# Color_Sorter_PROTOTYPE_v3_DMJ_Edit.net
KiCad netlist of a schematic drawn in EAGLE
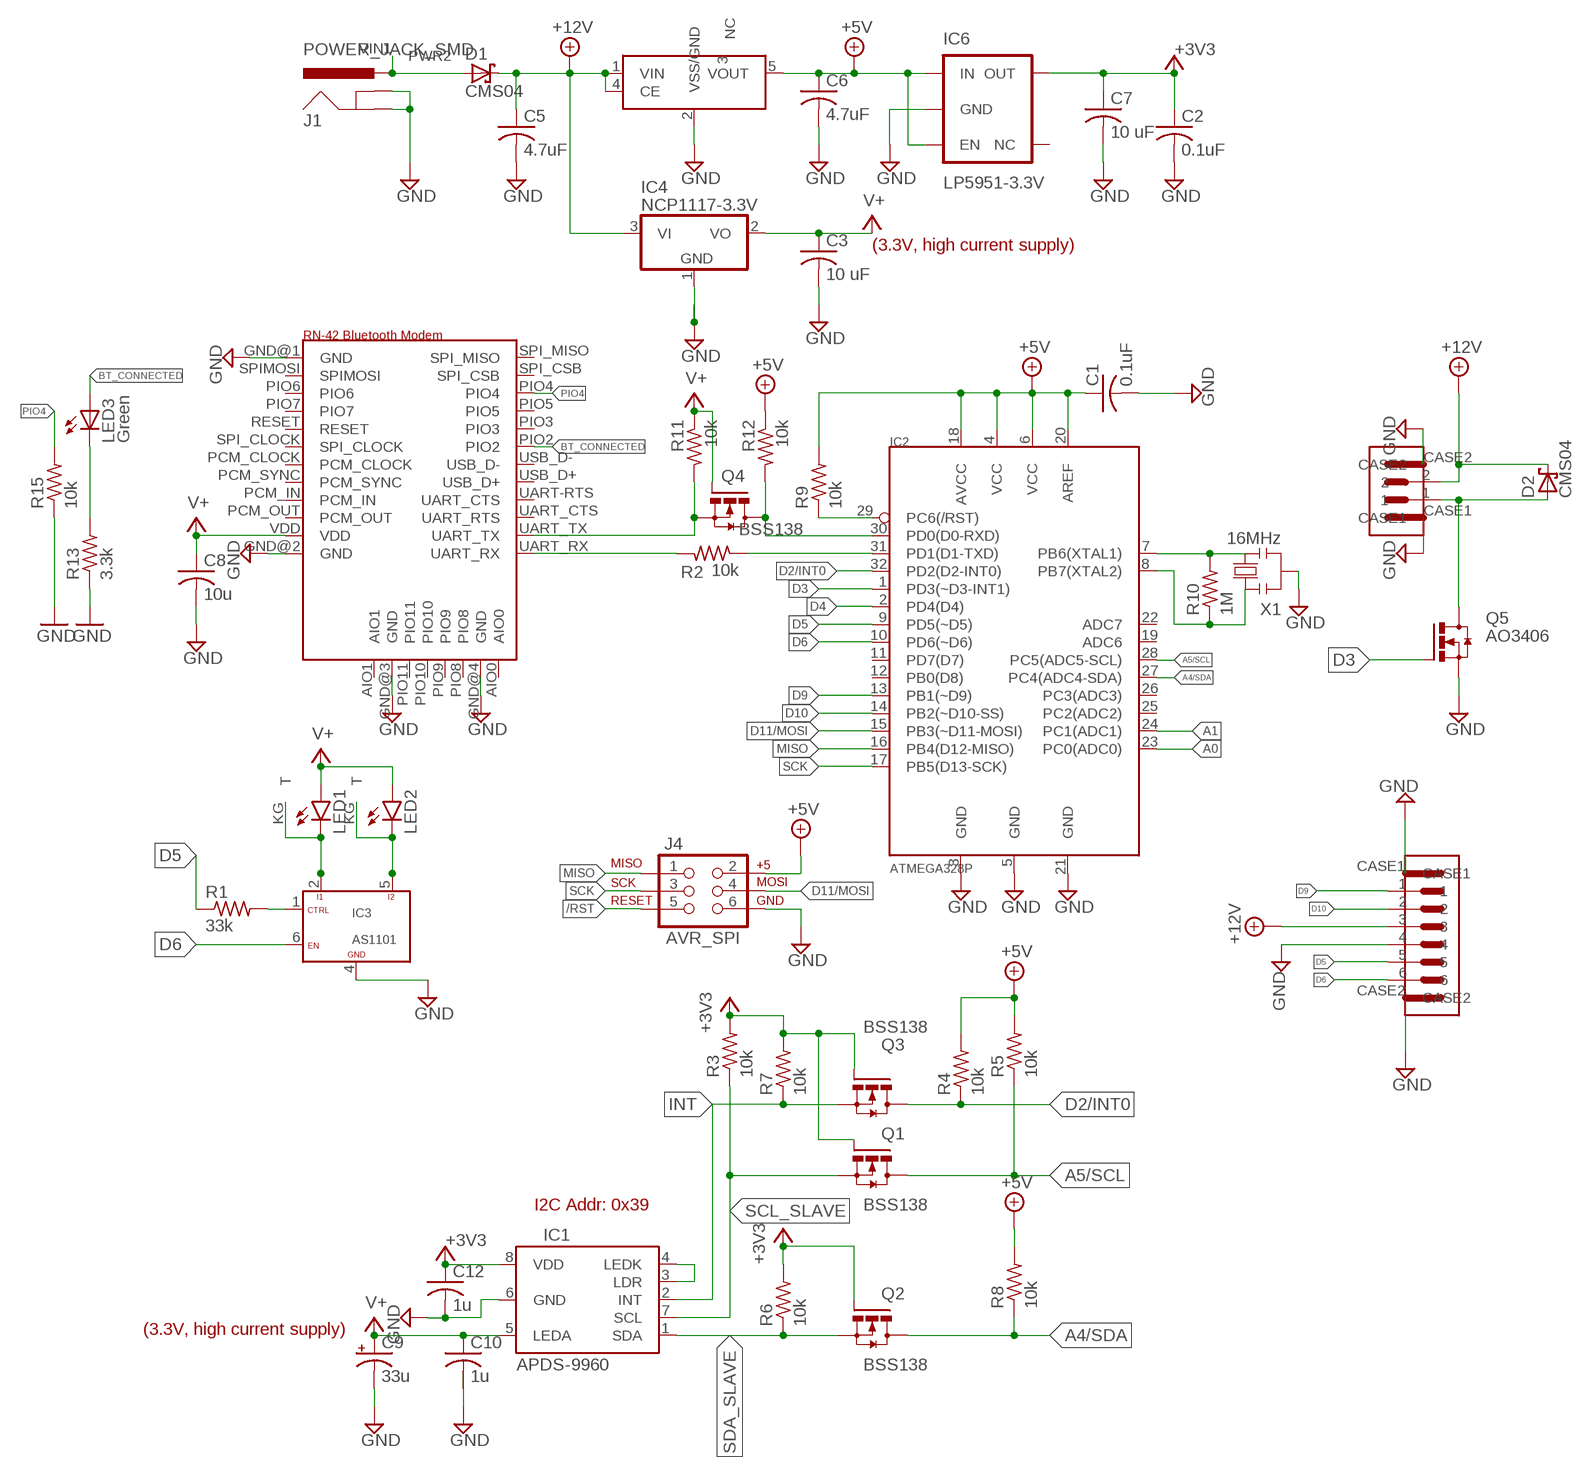
[diagram p0: schematic, sheet 1]

(export (version "E")
  (design (tool "Eeschema 10.0.6"))
  (components
    (comp (ref "A1")
      (value "RN-42_BLUETOOTH")
      (footprint "eagle-import:RN-42")
      (libsource (lib "eagle-import") (part "RN-42_BLUETOOTH"))
    )
    (comp (ref "C1")
      (value "0.1uF")
      (footprint "eagle-import:C0805")
      (libsource (lib "eagle-import") (part "C-USC0805"))
    )
    (comp (ref "C2")
      (value "0.1uF")
      (footprint "eagle-import:C0805")
      (libsource (lib "eagle-import") (part "C-USC0805"))
    )
    (comp (ref "C3")
      (value "10 uF")
      (footprint "eagle-import:C0805")
      (libsource (lib "eagle-import") (part "C-USC0805"))
    )
    (comp (ref "C5")
      (value "4.7uF")
      (footprint "eagle-import:C0805")
      (libsource (lib "eagle-import") (part "C-USC0805"))
    )
    (comp (ref "C6")
      (value "4.7uF")
      (footprint "eagle-import:C0805")
      (libsource (lib "eagle-import") (part "C-USC0805"))
    )
    (comp (ref "C7")
      (value "10 uF")
      (footprint "eagle-import:C0805")
      (libsource (lib "eagle-import") (part "C-USC0805"))
    )
    (comp (ref "C8")
      (value "10u")
      (footprint "eagle-import:C0805")
      (libsource (lib "eagle-import") (part "C-USC0805"))
    )
    (comp (ref "C9")
      (value "33u")
      (footprint "eagle-import:CT7343")
      (libsource (lib "eagle-import") (part "CPOL-USCT7343"))
    )
    (comp (ref "C10")
      (value "1u")
      (footprint "eagle-import:C0805")
      (libsource (lib "eagle-import") (part "C-USC0805"))
    )
    (comp (ref "C12")
      (value "1u")
      (footprint "eagle-import:C0805")
      (libsource (lib "eagle-import") (part "C-USC0805"))
    )
    (comp (ref "D1")
      (value "CMS04")
      (footprint "eagle-import:3-4E1A")
      (libsource (lib "eagle-import") (part "CMS04_SCHOTTKY"))
    )
    (comp (ref "D2")
      (value "CMS04")
      (footprint "eagle-import:3-4E1A")
      (libsource (lib "eagle-import") (part "CMS04_SCHOTTKY"))
    )
    (comp (ref "IC1")
      (value "APDS-9960")
      (footprint "eagle-import:SPARKFUN-SENSORS_APDS-9960")
      (libsource (lib "eagle-import") (part "SPARKFUN-SENSORS_APDS-9960"))
    )
    (comp (ref "IC2")
      (value "ATMEGA328P")
      (footprint "eagle-import:TQFP-32")
      (libsource (lib "eagle-import") (part "ATMEGA328P_TQFP"))
    )
    (comp (ref "IC3")
      (value "AS1101")
      (footprint "eagle-import:SC70-6")
      (libsource (lib "eagle-import") (part "AS1101-T"))
    )
    (comp (ref "IC4")
      (value "NCP1117-3.3V")
      (footprint "eagle-import:SOT-223")
      (libsource (lib "eagle-import") (part "NCP1117_REGULATOR"))
    )
    (comp (ref "IC5")
      (value "XC6701-5V")
      (footprint "eagle-import:DMJ_LINEAR_SOT23-5")
      (libsource (lib "eagle-import") (part "DMJ_LINEAR_XC6701B502"))
    )
    (comp (ref "IC6")
      (value "LP5951-3.3V")
      (footprint "eagle-import:SOT23-5")
      (libsource (lib "eagle-import") (part "LP5951-3.3V"))
    )
    (comp (ref "J1")
      (value "POWER_JACK_SMD")
      (footprint "eagle-import:SMD_POWER_JACK")
      (libsource (lib "eagle-import") (part "POWER_JACK_SMD"))
    )
    (comp (ref "J4")
      (value "AVR_SPI")
      (footprint "eagle-import:2X3")
      (libsource (lib "eagle-import") (part "AVR_SPI_PRG_6PTH"))
    )
    (comp (ref "LED1")
      (value "LED_SAMSUNG_SPMWHT541MD7WATMS0")
      (footprint "eagle-import:LED_SAMSUNG_SPMWHT541MD7WATMS0")
      (libsource (lib "eagle-import") (part "LED_SAMSUNG_SPMWHT541MD7WATMS0"))
    )
    (comp (ref "LED2")
      (value "LED_SAMSUNG_SPMWHT541MD7WATMS0")
      (footprint "eagle-import:LED_SAMSUNG_SPMWHT541MD7WATMS0")
      (libsource (lib "eagle-import") (part "LED_SAMSUNG_SPMWHT541MD7WATMS0"))
    )
    (comp (ref "LED3")
      (value "Green")
      (footprint "eagle-import:LED-1206")
      (libsource (lib "eagle-import") (part "LED1206"))
    )
    (comp (ref "Q1")
      (value "BSS138")
      (footprint "eagle-import:BE-420-CUSTOM-PARTS_SOT-23")
      (libsource (lib "eagle-import") (part "BE-420-CUSTOM-PARTS_BSS138_N_CHANNEL_MOSFET"))
    )
    (comp (ref "Q2")
      (value "BSS138")
      (footprint "eagle-import:BE-420-CUSTOM-PARTS_SOT-23")
      (libsource (lib "eagle-import") (part "BE-420-CUSTOM-PARTS_BSS138_N_CHANNEL_MOSFET"))
    )
    (comp (ref "Q3")
      (value "BSS138")
      (footprint "eagle-import:BE-420-CUSTOM-PARTS_SOT-23")
      (libsource (lib "eagle-import") (part "BE-420-CUSTOM-PARTS_BSS138_N_CHANNEL_MOSFET"))
    )
    (comp (ref "Q4")
      (value "BSS138")
      (footprint "eagle-import:BE-420-CUSTOM-PARTS_SOT-23")
      (libsource (lib "eagle-import") (part "BE-420-CUSTOM-PARTS_BSS138_N_CHANNEL_MOSFET"))
    )
    (comp (ref "Q5")
      (value "AO3406")
      (footprint "eagle-import:SOT-23-3")
      (libsource (lib "eagle-import") (part "N_PWR_MOSFET_AO3406"))
    )
    (comp (ref "R1")
      (value "33k")
      (footprint "eagle-import:R0805")
      (libsource (lib "eagle-import") (part "R-US_R0805"))
    )
    (comp (ref "R2")
      (value "10k")
      (footprint "eagle-import:R0805")
      (libsource (lib "eagle-import") (part "R-US_R0805"))
    )
    (comp (ref "R3")
      (value "10k")
      (footprint "eagle-import:R0805")
      (libsource (lib "eagle-import") (part "R-US_R0805"))
    )
    (comp (ref "R4")
      (value "10k")
      (footprint "eagle-import:R0805")
      (libsource (lib "eagle-import") (part "R-US_R0805"))
    )
    (comp (ref "R5")
      (value "10k")
      (footprint "eagle-import:R0805")
      (libsource (lib "eagle-import") (part "R-US_R0805"))
    )
    (comp (ref "R6")
      (value "10k")
      (footprint "eagle-import:R0805")
      (libsource (lib "eagle-import") (part "R-US_R0805"))
    )
    (comp (ref "R7")
      (value "10k")
      (footprint "eagle-import:R0805")
      (libsource (lib "eagle-import") (part "R-US_R0805"))
    )
    (comp (ref "R8")
      (value "10k")
      (footprint "eagle-import:R0805")
      (libsource (lib "eagle-import") (part "R-US_R0805"))
    )
    (comp (ref "R9")
      (value "10k")
      (footprint "eagle-import:R0805")
      (libsource (lib "eagle-import") (part "R-US_R0805"))
    )
    (comp (ref "R10")
      (value "1M")
      (footprint "eagle-import:R0805")
      (libsource (lib "eagle-import") (part "R-US_R0805"))
    )
    (comp (ref "R11")
      (value "10k")
      (footprint "eagle-import:R0805")
      (libsource (lib "eagle-import") (part "R-US_R0805"))
    )
    (comp (ref "R12")
      (value "10k")
      (footprint "eagle-import:R0805")
      (libsource (lib "eagle-import") (part "R-US_R0805"))
    )
    (comp (ref "R13")
      (value "3.3k")
      (footprint "eagle-import:R0805")
      (libsource (lib "eagle-import") (part "R-US_R0805"))
    )
    (comp (ref "R15")
      (value "10k")
      (footprint "eagle-import:R0805")
      (libsource (lib "eagle-import") (part "R-US_R0805"))
    )
    (comp (ref "U$4")
      (value "1A-JENKINS-PHOENIX-CONTACT-CONNECTORS_1A_JENKINS_2013_6PIN_SMD_PHOENIX_CONTACT")
      (footprint "eagle-import:1A-JENKINS-PHOENIX-CONTACT-CONNECTORS_1A_JENKINS_2013_6-PIN-R_A_PHOENIX_SMD")
      (libsource (lib "eagle-import") (part "1A-JENKINS-PHOENIX-CONTACT-CONNECTORS_1A_JENKINS_2013_6PIN_SMD_PHOENIX_CONTACT"))
    )
    (comp (ref "U$7")
      (value "1A_JENKINS_2013_2PIN_SMD_PHOENIX_CONTACT")
      (footprint "eagle-import:1A_JENKINS_2013_2-PIN-R_A_PHOENIX_SMD")
      (libsource (lib "eagle-import") (part "1A_JENKINS_2013_2PIN_SMD_PHOENIX_CONTACT"))
    )
    (comp (ref "X1")
      (value "16MHz")
      (footprint "eagle-import:1A_JENKINS_2013_RESONATOR_SMD")
      (libsource (lib "eagle-import") (part "1A_JENKINS_2013_CSTCE16MHZ"))
    )
  )
  (nets
    (net (code "1") (name "+3V3") (class "Default")
      (node (ref "C12") (pin "1") (pinfunction "1_1") (pintype "passive"))
      (node (ref "C2") (pin "1") (pinfunction "1_1") (pintype "passive"))
      (node (ref "C7") (pin "1") (pinfunction "1_1") (pintype "passive"))
      (node (ref "IC1") (pin "8") (pinfunction "VDD_8") (pintype "bidirectional"))
      (node (ref "IC6") (pin "5") (pinfunction "OUT_5") (pintype "passive"))
      (node (ref "Q1") (pin "1-G") (pinfunction "G_1-G") (pintype "passive"))
      (node (ref "Q2") (pin "1-G") (pinfunction "G_1-G") (pintype "passive"))
      (node (ref "Q3") (pin "1-G") (pinfunction "G_1-G") (pintype "passive"))
      (node (ref "R3") (pin "2") (pinfunction "2_2") (pintype "passive"))
      (node (ref "R6") (pin "2") (pinfunction "2_2") (pintype "passive"))
      (node (ref "R7") (pin "2") (pinfunction "2_2") (pintype "passive"))
    )
    (net (code "2") (name "+5V") (class "Default")
      (node (ref "C1") (pin "1") (pinfunction "1_1") (pintype "passive"))
      (node (ref "C6") (pin "1") (pinfunction "1_1") (pintype "passive"))
      (node (ref "IC2") (pin "18") (pinfunction "AVCC_18") (pintype "bidirectional"))
      (node (ref "IC2") (pin "20") (pinfunction "AREF_20") (pintype "bidirectional"))
      (node (ref "IC2") (pin "4") (pinfunction "VCC_4") (pintype "bidirectional"))
      (node (ref "IC2") (pin "6") (pinfunction "VCC_6") (pintype "bidirectional"))
      (node (ref "IC5") (pin "5") (pinfunction "VOUT_5") (pintype "bidirectional"))
      (node (ref "IC6") (pin "1") (pinfunction "IN_1") (pintype "input"))
      (node (ref "IC6") (pin "3") (pinfunction "EN_3") (pintype "input"))
      (node (ref "J4") (pin "2") (pinfunction "2_2") (pintype "passive"))
      (node (ref "R12") (pin "1") (pinfunction "1_1") (pintype "passive"))
      (node (ref "R4") (pin "2") (pinfunction "2_2") (pintype "passive"))
      (node (ref "R5") (pin "2") (pinfunction "2_2") (pintype "passive"))
      (node (ref "R8") (pin "2") (pinfunction "2_2") (pintype "passive"))
      (node (ref "R9") (pin "2") (pinfunction "2_2") (pintype "passive"))
    )
    (net (code "3") (name "+12V") (class "Default")
      (node (ref "C5") (pin "1") (pinfunction "1_1") (pintype "passive"))
      (node (ref "D1") (pin "C") (pinfunction "C_C") (pintype "passive"))
      (node (ref "D2") (pin "C") (pinfunction "C_C") (pintype "passive"))
      (node (ref "IC4") (pin "3") (pinfunction "VI_3") (pintype "input"))
      (node (ref "IC5") (pin "1") (pinfunction "VIN_1") (pintype "bidirectional"))
      (node (ref "IC5") (pin "4") (pinfunction "CE_4") (pintype "bidirectional"))
      (node (ref "U$4") (pin "3") (pinfunction "3_3") (pintype "bidirectional"))
      (node (ref "U$7") (pin "2") (pinfunction "2_2") (pintype "bidirectional"))
    )
    (net (code "4") (name "A0") (class "Default")
      (node (ref "IC2") (pin "23") (pinfunction "PC0(ADC0)_23") (pintype "bidirectional"))
    )
    (net (code "5") (name "A1") (class "Default")
      (node (ref "IC2") (pin "24") (pinfunction "PC1(ADC1)_24") (pintype "bidirectional"))
    )
    (net (code "6") (name "A4{slash}SDA") (class "Default")
      (node (ref "IC2") (pin "27") (pinfunction "PC4(ADC4-SDA)_27") (pintype "bidirectional"))
      (node (ref "Q2") (pin "3-D") (pinfunction "D_3-D") (pintype "passive"))
      (node (ref "R8") (pin "1") (pinfunction "1_1") (pintype "passive"))
    )
    (net (code "7") (name "A5{slash}SCL") (class "Default")
      (node (ref "IC2") (pin "28") (pinfunction "PC5(ADC5-SCL)_28") (pintype "bidirectional"))
      (node (ref "Q1") (pin "3-D") (pinfunction "D_3-D") (pintype "passive"))
      (node (ref "R5") (pin "1") (pinfunction "1_1") (pintype "passive"))
    )
    (net (code "8") (name "BT_CONNECTED") (class "Default")
      (node (ref "A1") (pin "PIO2") (pinfunction "PIO2_PIO2") (pintype "bidirectional"))
      (node (ref "LED3") (pin "A") (pinfunction "A_A") (pintype "passive"))
    )
    (net (code "9") (name "D2{slash}INT0") (class "Default")
      (node (ref "IC2") (pin "32") (pinfunction "PD2(D2-INT0)_32") (pintype "bidirectional"))
      (node (ref "Q3") (pin "3-D") (pinfunction "D_3-D") (pintype "passive"))
      (node (ref "R4") (pin "1") (pinfunction "1_1") (pintype "passive"))
    )
    (net (code "10") (name "D3") (class "Default")
      (node (ref "IC2") (pin "1") (pinfunction "PD3(~{D3-INT1})_1") (pintype "bidirectional"))
      (node (ref "Q5") (pin "1") (pinfunction "G_1") (pintype "passive"))
    )
    (net (code "11") (name "D4") (class "Default")
      (node (ref "IC2") (pin "2") (pinfunction "PD4(D4)_2") (pintype "bidirectional"))
    )
    (net (code "12") (name "D5") (class "Default")
      (node (ref "IC2") (pin "9") (pinfunction "PD5(~{D5})_9") (pintype "bidirectional"))
      (node (ref "R1") (pin "1") (pinfunction "1_1") (pintype "passive"))
      (node (ref "U$4") (pin "5") (pinfunction "5_5") (pintype "bidirectional"))
    )
    (net (code "13") (name "D6") (class "Default")
      (node (ref "IC2") (pin "10") (pinfunction "PD6(~{D6})_10") (pintype "bidirectional"))
      (node (ref "IC3") (pin "6") (pinfunction "EN_6") (pintype "bidirectional"))
      (node (ref "U$4") (pin "6") (pinfunction "6_6") (pintype "bidirectional"))
    )
    (net (code "14") (name "D9") (class "Default")
      (node (ref "IC2") (pin "13") (pinfunction "PB1(~{D9})_13") (pintype "bidirectional"))
      (node (ref "U$4") (pin "1") (pinfunction "1_1") (pintype "bidirectional"))
    )
    (net (code "15") (name "D10") (class "Default")
      (node (ref "IC2") (pin "14") (pinfunction "PB2(~{D10-SS})_14") (pintype "bidirectional"))
      (node (ref "U$4") (pin "2") (pinfunction "2_2") (pintype "bidirectional"))
    )
    (net (code "16") (name "D11{slash}MOSI") (class "Default")
      (node (ref "IC2") (pin "15") (pinfunction "PB3(~{D11-MOSI})_15") (pintype "bidirectional"))
      (node (ref "J4") (pin "4") (pinfunction "4_4") (pintype "passive"))
    )
    (net (code "17") (name "GND") (class "Default")
      (node (ref "A1") (pin "GND@1") (pinfunction "GND_GND@1") (pintype "bidirectional"))
      (node (ref "A1") (pin "GND@2") (pinfunction "GND_GND@2") (pintype "bidirectional"))
      (node (ref "A1") (pin "GND@3") (pinfunction "GND_GND@3") (pintype "bidirectional"))
      (node (ref "A1") (pin "GND@4") (pinfunction "GND_GND@4") (pintype "bidirectional"))
      (node (ref "C1") (pin "2") (pinfunction "2_2") (pintype "passive"))
      (node (ref "C10") (pin "2") (pinfunction "2_2") (pintype "passive"))
      (node (ref "C12") (pin "2") (pinfunction "2_2") (pintype "passive"))
      (node (ref "C2") (pin "2") (pinfunction "2_2") (pintype "passive"))
      (node (ref "C3") (pin "2") (pinfunction "2_2") (pintype "passive"))
      (node (ref "C5") (pin "2") (pinfunction "2_2") (pintype "passive"))
      (node (ref "C6") (pin "2") (pinfunction "2_2") (pintype "passive"))
      (node (ref "C7") (pin "2") (pinfunction "2_2") (pintype "passive"))
      (node (ref "C8") (pin "2") (pinfunction "2_2") (pintype "passive"))
      (node (ref "C9") (pin "-") (pinfunction "-_-") (pintype "passive"))
      (node (ref "IC1") (pin "6") (pinfunction "GND_6") (pintype "bidirectional"))
      (node (ref "IC2") (pin "21") (pinfunction "GND_21") (pintype "bidirectional"))
      (node (ref "IC2") (pin "3") (pinfunction "GND_3") (pintype "bidirectional"))
      (node (ref "IC2") (pin "5") (pinfunction "GND_5") (pintype "bidirectional"))
      (node (ref "IC3") (pin "4") (pinfunction "GND_4") (pintype "bidirectional"))
      (node (ref "IC4") (pin "1") (pinfunction "GND_1") (pintype "passive"))
      (node (ref "IC5") (pin "2") (pinfunction "VSS/GND_2") (pintype "bidirectional"))
      (node (ref "IC6") (pin "2") (pinfunction "GND_2") (pintype "input"))
      (node (ref "J1") (pin "GND") (pinfunction "GND_GND") (pintype "bidirectional"))
      (node (ref "J1") (pin "P$4") (pinfunction "GNDBREAK_P$4") (pintype "bidirectional"))
      (node (ref "J4") (pin "6") (pinfunction "6_6") (pintype "passive"))
      (node (ref "Q5") (pin "2") (pinfunction "S_2") (pintype "passive"))
      (node (ref "R13") (pin "1") (pinfunction "1_1") (pintype "passive"))
      (node (ref "R15") (pin "1") (pinfunction "1_1") (pintype "passive"))
      (node (ref "U$4") (pin "4") (pinfunction "4_4") (pintype "bidirectional"))
      (node (ref "U$4") (pin "CASE1") (pinfunction "CASE1_CASE1") (pintype "bidirectional"))
      (node (ref "U$4") (pin "CASE2") (pinfunction "CASE2_CASE2") (pintype "bidirectional"))
      (node (ref "U$7") (pin "CASE1") (pinfunction "CASE1_CASE1") (pintype "bidirectional"))
      (node (ref "U$7") (pin "CASE2") (pinfunction "CASE2_CASE2") (pintype "bidirectional"))
      (node (ref "X1") (pin "2") (pinfunction "2_2") (pintype "passive"))
    )
    (net (code "18") (name "INT") (class "Default")
      (node (ref "IC1") (pin "2") (pinfunction "INT_2") (pintype "bidirectional"))
      (node (ref "Q3") (pin "2-S") (pinfunction "S_2-S") (pintype "passive"))
      (node (ref "R7") (pin "1") (pinfunction "1_1") (pintype "passive"))
    )
    (net (code "19") (name "MISO") (class "Default")
      (node (ref "IC2") (pin "16") (pinfunction "PB4(D12-MISO)_16") (pintype "bidirectional"))
      (node (ref "J4") (pin "1") (pinfunction "1_1") (pintype "passive"))
    )
    (net (code "20") (name "Net-(A1-PadUART_RX)") (class "Default")
      (node (ref "A1") (pin "UART_RX") (pinfunction "UART_RX_UART_RX") (pintype "bidirectional"))
      (node (ref "R2") (pin "2") (pinfunction "2_2") (pintype "passive"))
    )
    (net (code "21") (name "Net-(IC1-LDR)") (class "Default")
      (node (ref "IC1") (pin "3") (pinfunction "LDR_3") (pintype "bidirectional"))
      (node (ref "IC1") (pin "4") (pinfunction "LEDK_4") (pintype "bidirectional"))
    )
    (net (code "22") (name "Net-(IC2-PB6(XTAL1))") (class "Default")
      (node (ref "IC2") (pin "7") (pinfunction "PB6(XTAL1)_7") (pintype "bidirectional"))
      (node (ref "R10") (pin "2") (pinfunction "2_2") (pintype "passive"))
      (node (ref "X1") (pin "3") (pinfunction "3_3") (pintype "passive"))
    )
    (net (code "23") (name "Net-(IC2-PB7(XTAL2))") (class "Default")
      (node (ref "IC2") (pin "8") (pinfunction "PB7(XTAL2)_8") (pintype "bidirectional"))
      (node (ref "R10") (pin "1") (pinfunction "1_1") (pintype "passive"))
      (node (ref "X1") (pin "1") (pinfunction "1_1") (pintype "passive"))
    )
    (net (code "24") (name "Net-(IC2-PD0(D0-RXD))") (class "Default")
      (node (ref "IC2") (pin "30") (pinfunction "PD0(D0-RXD)_30") (pintype "bidirectional"))
      (node (ref "Q4") (pin "3-D") (pinfunction "D_3-D") (pintype "passive"))
      (node (ref "R12") (pin "2") (pinfunction "2_2") (pintype "passive"))
    )
    (net (code "25") (name "Net-(IC2-PD1(D1-TXD))") (class "Default")
      (node (ref "IC2") (pin "31") (pinfunction "PD1(D1-TXD)_31") (pintype "bidirectional"))
      (node (ref "R2") (pin "1") (pinfunction "1_1") (pintype "passive"))
    )
    (net (code "26") (name "Net-(IC3-CTRL)") (class "Default")
      (node (ref "IC3") (pin "1") (pinfunction "CTRL_1") (pintype "bidirectional"))
      (node (ref "R1") (pin "2") (pinfunction "2_2") (pintype "passive"))
    )
    (net (code "27") (name "Net-(IC3-I1)") (class "Default")
      (node (ref "IC3") (pin "2") (pinfunction "I1_2") (pintype "bidirectional"))
      (node (ref "LED1") (pin "KA") (pinfunction "C_KA") (pintype "passive"))
      (node (ref "LED1") (pin "KG") (pinfunction "T_KG") (pintype "bidirectional"))
    )
    (net (code "28") (name "Net-(IC3-I2)") (class "Default")
      (node (ref "IC3") (pin "5") (pinfunction "I2_5") (pintype "bidirectional"))
      (node (ref "LED2") (pin "KA") (pinfunction "C_KA") (pintype "passive"))
      (node (ref "LED2") (pin "KG") (pinfunction "T_KG") (pintype "bidirectional"))
    )
    (net (code "29") (name "Net-(J1-PWR)") (class "Default")
      (node (ref "D1") (pin "A") (pinfunction "A_A") (pintype "passive"))
      (node (ref "J1") (pin "VIN0") (pinfunction "PWR_VIN0") (pintype "bidirectional"))
      (node (ref "J1") (pin "VIN1") (pinfunction "PWR2_VIN1") (pintype "bidirectional"))
    )
    (net (code "30") (name "Net-(LED3-PadC)") (class "Default")
      (node (ref "LED3") (pin "C") (pinfunction "C_C") (pintype "passive"))
      (node (ref "R13") (pin "2") (pinfunction "2_2") (pintype "passive"))
    )
    (net (code "31") (name "Net-(Q4-S)") (class "Default")
      (node (ref "A1") (pin "UART_TX") (pinfunction "UART_TX_UART_TX") (pintype "bidirectional"))
      (node (ref "Q4") (pin "2-S") (pinfunction "S_2-S") (pintype "passive"))
      (node (ref "R11") (pin "2") (pinfunction "2_2") (pintype "passive"))
    )
    (net (code "32") (name "Net-(Q5-D)") (class "Default")
      (node (ref "D2") (pin "A") (pinfunction "A_A") (pintype "passive"))
      (node (ref "Q5") (pin "3") (pinfunction "D_3") (pintype "passive"))
      (node (ref "U$7") (pin "1") (pinfunction "1_1") (pintype "bidirectional"))
    )
    (net (code "33") (name "PIO4") (class "Default")
      (node (ref "A1") (pin "PIO4") (pinfunction "PIO4_PIO4") (pintype "bidirectional"))
      (node (ref "R15") (pin "2") (pinfunction "2_2") (pintype "passive"))
    )
    (net (code "34") (name "SCK") (class "Default")
      (node (ref "IC2") (pin "17") (pinfunction "PB5(D13-SCK)_17") (pintype "bidirectional"))
      (node (ref "J4") (pin "3") (pinfunction "3_3") (pintype "passive"))
    )
    (net (code "35") (name "SCL_SLAVE") (class "Default")
      (node (ref "IC1") (pin "7") (pinfunction "SCL_7") (pintype "bidirectional"))
      (node (ref "Q1") (pin "2-S") (pinfunction "S_2-S") (pintype "passive"))
      (node (ref "R3") (pin "1") (pinfunction "1_1") (pintype "passive"))
    )
    (net (code "36") (name "SDA_SLAVE") (class "Default")
      (node (ref "IC1") (pin "1") (pinfunction "SDA_1") (pintype "bidirectional"))
      (node (ref "Q2") (pin "2-S") (pinfunction "S_2-S") (pintype "passive"))
      (node (ref "R6") (pin "1") (pinfunction "1_1") (pintype "passive"))
    )
    (net (code "37") (name "V+") (class "Default")
      (node (ref "A1") (pin "VDD") (pinfunction "VDD_VDD") (pintype "bidirectional"))
      (node (ref "C10") (pin "1") (pinfunction "1_1") (pintype "passive"))
      (node (ref "C3") (pin "1") (pinfunction "1_1") (pintype "passive"))
      (node (ref "C8") (pin "1") (pinfunction "1_1") (pintype "passive"))
      (node (ref "C9") (pin "+") (pinfunction "+_+") (pintype "passive"))
      (node (ref "IC1") (pin "5") (pinfunction "LEDA_5") (pintype "bidirectional"))
      (node (ref "IC4") (pin "2") (pinfunction "VO_2") (pintype "passive"))
      (node (ref "LED1") (pin "A") (pinfunction "A_A") (pintype "passive"))
      (node (ref "LED2") (pin "A") (pinfunction "A_A") (pintype "passive"))
      (node (ref "Q4") (pin "1-G") (pinfunction "G_1-G") (pintype "passive"))
      (node (ref "R11") (pin "1") (pinfunction "1_1") (pintype "passive"))
    )
    (net (code "38") (name "unconnected-(A1-PadAIO0)") (class "Default")
      (node (ref "A1") (pin "AIO0") (pinfunction "AIO0_AIO0") (pintype "bidirectional"))
    )
    (net (code "39") (name "unconnected-(A1-PadAIO1)") (class "Default")
      (node (ref "A1") (pin "AIO1") (pinfunction "AIO1_AIO1") (pintype "bidirectional"))
    )
    (net (code "40") (name "unconnected-(A1-PadPCM_CLOCK)") (class "Default")
      (node (ref "A1") (pin "PCM_CLOCK") (pinfunction "PCM_CLOCK_PCM_CLOCK") (pintype "bidirectional"))
    )
    (net (code "41") (name "unconnected-(A1-PadPCM_IN)") (class "Default")
      (node (ref "A1") (pin "PCM_IN") (pinfunction "PCM_IN_PCM_IN") (pintype "bidirectional"))
    )
    (net (code "42") (name "unconnected-(A1-PadPCM_OUT)") (class "Default")
      (node (ref "A1") (pin "PCM_OUT") (pinfunction "PCM_OUT_PCM_OUT") (pintype "bidirectional"))
    )
    (net (code "43") (name "unconnected-(A1-PadPCM_SYNC)") (class "Default")
      (node (ref "A1") (pin "PCM_SYNC") (pinfunction "PCM_SYNC_PCM_SYNC") (pintype "bidirectional"))
    )
    (net (code "44") (name "unconnected-(A1-PadPIO3)") (class "Default")
      (node (ref "A1") (pin "PIO3") (pinfunction "PIO3_PIO3") (pintype "bidirectional"))
    )
    (net (code "45") (name "unconnected-(A1-PadPIO5)") (class "Default")
      (node (ref "A1") (pin "PIO5") (pinfunction "PIO5_PIO5") (pintype "bidirectional"))
    )
    (net (code "46") (name "unconnected-(A1-PadPIO6)") (class "Default")
      (node (ref "A1") (pin "PIO6") (pinfunction "PIO6_PIO6") (pintype "bidirectional"))
    )
    (net (code "47") (name "unconnected-(A1-PadPIO7)") (class "Default")
      (node (ref "A1") (pin "PIO7") (pinfunction "PIO7_PIO7") (pintype "bidirectional"))
    )
    (net (code "48") (name "unconnected-(A1-PadPIO8)") (class "Default")
      (node (ref "A1") (pin "PIO8") (pinfunction "PIO8_PIO8") (pintype "bidirectional"))
    )
    (net (code "49") (name "unconnected-(A1-PadPIO9)") (class "Default")
      (node (ref "A1") (pin "PIO9") (pinfunction "PIO9_PIO9") (pintype "bidirectional"))
    )
    (net (code "50") (name "unconnected-(A1-PadPIO10)") (class "Default")
      (node (ref "A1") (pin "PIO10") (pinfunction "PIO10_PIO10") (pintype "bidirectional"))
    )
    (net (code "51") (name "unconnected-(A1-PadPIO11)") (class "Default")
      (node (ref "A1") (pin "PIO11") (pinfunction "PIO11_PIO11") (pintype "bidirectional"))
    )
    (net (code "52") (name "unconnected-(A1-PadRESET)") (class "Default")
      (node (ref "A1") (pin "RESET") (pinfunction "RESET_RESET") (pintype "bidirectional"))
    )
    (net (code "53") (name "unconnected-(A1-PadSPIMOSI)") (class "Default")
      (node (ref "A1") (pin "SPIMOSI") (pinfunction "SPIMOSI_SPIMOSI") (pintype "bidirectional"))
    )
    (net (code "54") (name "unconnected-(A1-PadSPI_CLOCK)") (class "Default")
      (node (ref "A1") (pin "SPI_CLOCK") (pinfunction "SPI_CLOCK_SPI_CLOCK") (pintype "bidirectional"))
    )
    (net (code "55") (name "unconnected-(A1-PadSPI_CSB)") (class "Default")
      (node (ref "A1") (pin "SPI_CSB") (pinfunction "SPI_CSB_SPI_CSB") (pintype "bidirectional"))
    )
    (net (code "56") (name "unconnected-(A1-PadSPI_MISO)") (class "Default")
      (node (ref "A1") (pin "SPI_MISO") (pinfunction "SPI_MISO_SPI_MISO") (pintype "bidirectional"))
    )
    (net (code "57") (name "unconnected-(A1-PadUSB_D+)") (class "Default")
      (node (ref "A1") (pin "USB_D+") (pinfunction "USB_D+_USB_D+") (pintype "bidirectional"))
    )
    (net (code "58") (name "unconnected-(A1-PadUSB_D-)") (class "Default")
      (node (ref "A1") (pin "USB_D-") (pinfunction "USB_D-_USB_D-") (pintype "bidirectional"))
    )
    (net (code "59") (name "unconnected-(A1-UART_CTS-PadUART-RTS)") (class "Default")
      (node (ref "A1") (pin "UART-RTS") (pinfunction "UART_CTS_UART-RTS") (pintype "bidirectional"))
    )
    (net (code "60") (name "unconnected-(A1-UART_RTS-PadUART_CTS)") (class "Default")
      (node (ref "A1") (pin "UART_CTS") (pinfunction "UART_RTS_UART_CTS") (pintype "bidirectional"))
    )
    (net (code "61") (name "unconnected-(IC2-ADC6-Pad19)") (class "Default")
      (node (ref "IC2") (pin "19") (pinfunction "ADC6_19") (pintype "bidirectional"))
    )
    (net (code "62") (name "unconnected-(IC2-ADC7-Pad22)") (class "Default")
      (node (ref "IC2") (pin "22") (pinfunction "ADC7_22") (pintype "bidirectional"))
    )
    (net (code "63") (name "unconnected-(IC2-PB0(D8)-Pad12)") (class "Default")
      (node (ref "IC2") (pin "12") (pinfunction "PB0(D8)_12") (pintype "bidirectional"))
    )
    (net (code "64") (name "unconnected-(IC2-PC2(ADC2)-Pad25)") (class "Default")
      (node (ref "IC2") (pin "25") (pinfunction "PC2(ADC2)_25") (pintype "bidirectional"))
    )
    (net (code "65") (name "unconnected-(IC2-PC3(ADC3)-Pad26)") (class "Default")
      (node (ref "IC2") (pin "26") (pinfunction "PC3(ADC3)_26") (pintype "bidirectional"))
    )
    (net (code "66") (name "unconnected-(IC2-PD7(D7)-Pad11)") (class "Default")
      (node (ref "IC2") (pin "11") (pinfunction "PD7(D7)_11") (pintype "bidirectional"))
    )
    (net (code "67") (name "unconnected-(IC5-NC-Pad3)") (class "Default")
      (node (ref "IC5") (pin "3") (pinfunction "NC_3") (pintype "bidirectional"))
    )
    (net (code "68") (name "unconnected-(IC6-NC-Pad4)") (class "Default")
      (node (ref "IC6") (pin "4") (pinfunction "NC_4") (pintype "input"))
    )
    (net (code "69") (name "{slash}RST") (class "Default")
      (node (ref "IC2") (pin "29") (pinfunction "PC6(/RST)_29") (pintype "bidirectional"))
      (node (ref "J4") (pin "5") (pinfunction "5_5") (pintype "passive"))
      (node (ref "R9") (pin "1") (pinfunction "1_1") (pintype "passive"))
    )
  )
)
